# Offboard.net
KiCad netlist of a schematic drawn in Altium Designer
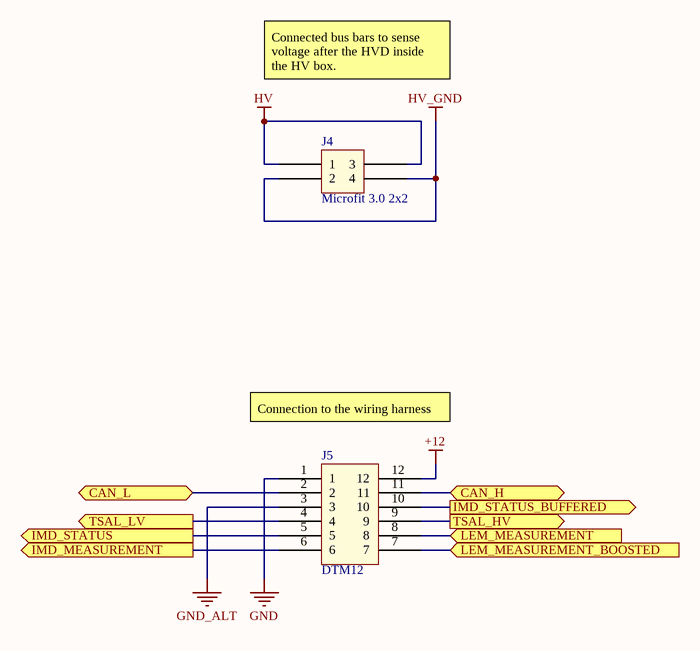
[diagram p0: Offboard.SchDoc]

(export (version "E")
  (design (tool "Eeschema 10.0.6"))
  (components
    (comp (ref "J4")
      (value "Microfit 3.0 2x2")
      (footprint "Microfit_2X2_R_TH")
      (libsource (lib "QUTMS_Microfit") (part "Microfit_2x2"))
    )
    (comp (ref "J5")
      (value "DTM12")
      (footprint "DTM13-12PA")
      (libsource (lib "QUTMS_DeutschPCB") (part "DTM12"))
    )
  )
  (nets
    (net (code "1") (name "+12") (class "Default")
      (node (ref "J5") (pin "12") (pinfunction "12_12") (pintype "passive"))
    )
    (net (code "2") (name "/CAN_H") (class "Default")
      (node (ref "J5") (pin "11") (pinfunction "11_11") (pintype "passive"))
    )
    (net (code "3") (name "/CAN_L") (class "Default")
      (node (ref "J5") (pin "2") (pinfunction "2_2") (pintype "passive"))
    )
    (net (code "4") (name "/IMD_MEASUREMENT") (class "Default")
      (node (ref "J5") (pin "6") (pinfunction "6_6") (pintype "passive"))
    )
    (net (code "5") (name "/IMD_STATUS") (class "Default")
      (node (ref "J5") (pin "5") (pinfunction "5_5") (pintype "passive"))
    )
    (net (code "6") (name "/IMD_STATUS_BUFFERED") (class "Default")
      (node (ref "J5") (pin "10") (pinfunction "10_10") (pintype "passive"))
    )
    (net (code "7") (name "/LEM_MEASUREMENT") (class "Default")
      (node (ref "J5") (pin "8") (pinfunction "8_8") (pintype "passive"))
    )
    (net (code "8") (name "/LEM_MEASUREMENT_BOOSTED") (class "Default")
      (node (ref "J5") (pin "7") (pinfunction "7_7") (pintype "passive"))
    )
    (net (code "9") (name "/TSAL_HV") (class "Default")
      (node (ref "J5") (pin "9") (pinfunction "9_9") (pintype "passive"))
    )
    (net (code "10") (name "/TSAL_LV") (class "Default")
      (node (ref "J5") (pin "4") (pinfunction "4_4") (pintype "passive"))
    )
    (net (code "11") (name "GND") (class "Default")
      (node (ref "J5") (pin "1") (pinfunction "1_1") (pintype "passive"))
    )
    (net (code "12") (name "GND_ALT") (class "Default")
      (node (ref "J5") (pin "3") (pinfunction "3_3") (pintype "passive"))
    )
    (net (code "13") (name "HV") (class "Default")
      (node (ref "J4") (pin "1") (pinfunction "1_1") (pintype "passive"))
      (node (ref "J4") (pin "3") (pinfunction "3_3") (pintype "passive"))
    )
    (net (code "14") (name "HV_GND") (class "Default")
      (node (ref "J4") (pin "2") (pinfunction "2_2") (pintype "passive"))
      (node (ref "J4") (pin "4") (pinfunction "4_4") (pintype "passive"))
    )
  )
)
